# bmsMaster_power.net
KiCad netlist of a schematic drawn in Altium Designer
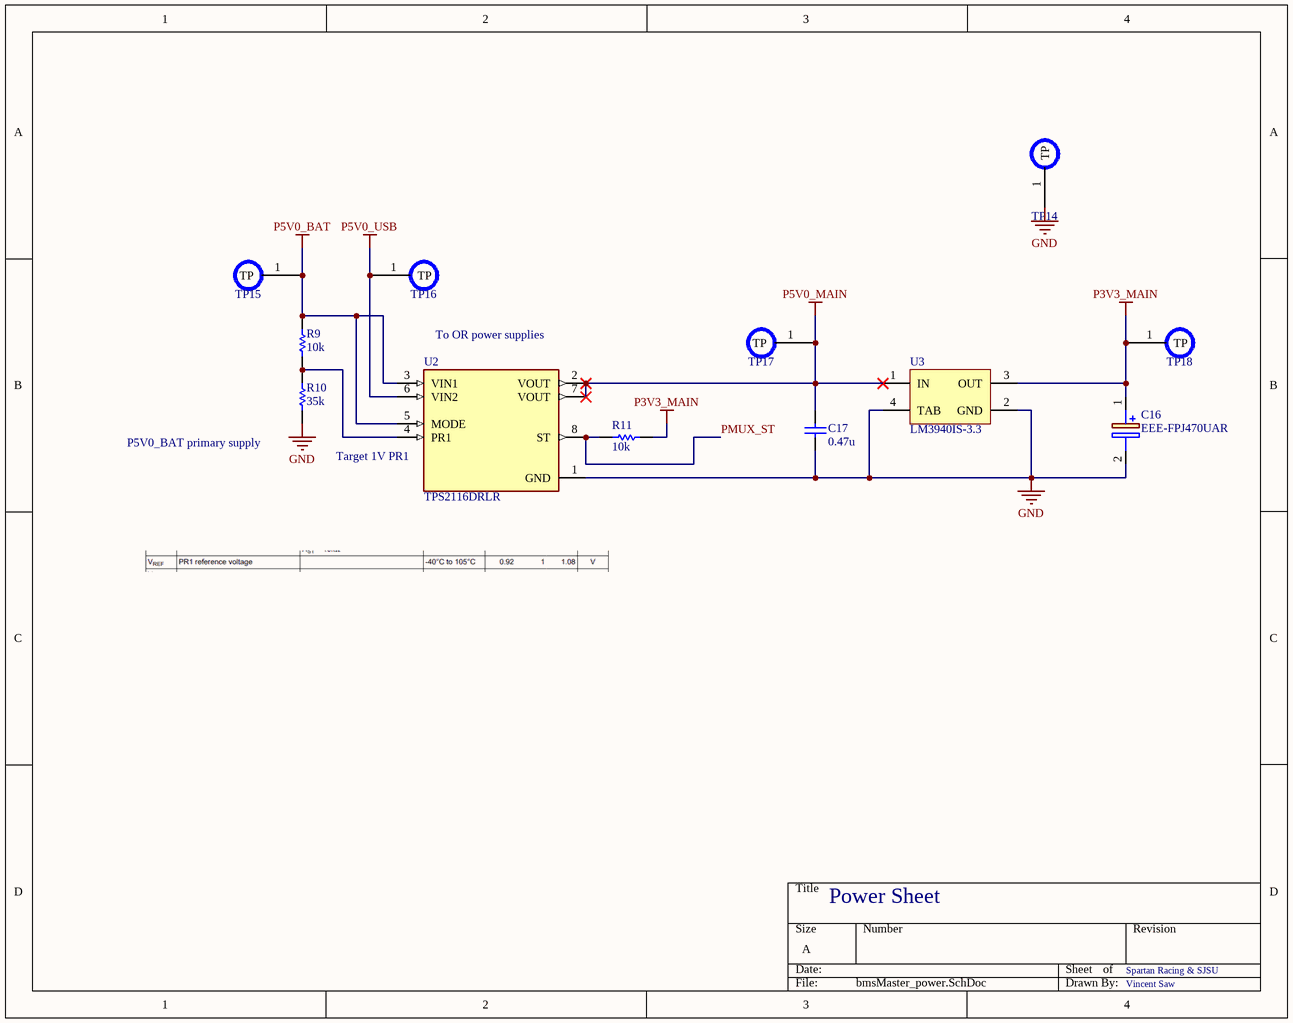
[diagram p0: bmsMaster_power.SchDoc]

(export (version "E")
  (design (tool "Eeschema 10.0.6"))
  (components
    (comp (ref "C16")
      (value "EEE-FPJ470UAR")
      (footprint "SamacSys:EEE1AA220WR")
      (description "Capacitor Polarised")
      (fields (field (name "MOUSER PART NUMBER") "667-EEE-FPJ470UAR"))
      (libsource (lib "*") (part "EEE-FPJ470UAR"))
    )
    (comp (ref "C17")
      (value "0.47u")
      (footprint "CAPC1608X90N")
      (description "Capacitor")
      (libsource (lib "Simulation Generic Components") (part "Capacitor"))
    )
    (comp (ref "R9")
      (value "10k")
      (footprint "RESC1608X50N")
      (description "Resistor")
      (libsource (lib "Simulation Generic Components") (part "Resistor"))
    )
    (comp (ref "R10")
      (value "35k")
      (footprint "RESC1608X50N")
      (description "Resistor")
      (libsource (lib "Simulation Generic Components") (part "Resistor"))
    )
    (comp (ref "R11")
      (value "10k")
      (footprint "RESC1608X50N")
      (description "Resistor")
      (libsource (lib "Simulation Generic Components") (part "Resistor"))
    )
    (comp (ref "TP14")
      (value "TSTPT")
      (footprint "Testpoint1")
      (libsource (lib "testpoint1") (part "Testpoint1"))
    )
    (comp (ref "TP15")
      (value "TSTPT")
      (footprint "Testpoint1")
      (libsource (lib "testpoint1") (part "Testpoint1"))
    )
    (comp (ref "TP16")
      (value "TSTPT")
      (footprint "Testpoint1")
      (libsource (lib "testpoint1") (part "Testpoint1"))
    )
    (comp (ref "TP17")
      (value "TSTPT")
      (footprint "Testpoint1")
      (libsource (lib "testpoint1") (part "Testpoint1"))
    )
    (comp (ref "TP18")
      (value "TSTPT")
      (footprint "Testpoint1")
      (libsource (lib "testpoint1") (part "Testpoint1"))
    )
    (comp (ref "U2")
      (value "TPS2116DRLR")
      (footprint "TPS2116DRLR:SOTFL50P160X60-8N")
      (description "1.6 V to 5.5 V, 2.5-A Low IQ Power Mux with Manual and Priority Switchover")
      (fields (field (name "MF") "{'manufacturer': u'Texas Instruments'}"))
      (libsource (lib "*") (part "TPS2116DRLR"))
    )
    (comp (ref "U3")
      (value "LM3940IS-3.3")
      (footprint "KTT0003B_N")
      (description "1A Low Dropout Regulator for 5V to 3.3V Conversion, 3-pin TO-263")
      (fields (field (name "MANUFACTURER") "Texas Instruments"))
      (libsource (lib "Altium Content Vault") (part "PM-REG-LM2940-TO4"))
    )
  )
  (nets
    (net (code "1") (name "/PMUX_ST") (class "Default")
      (node (ref "R11") (pin "2") (pinfunction "2_2") (pintype "passive"))
      (node (ref "U2") (pin "8") (pinfunction "ST_8") (pintype "output"))
    )
    (net (code "2") (name "GND") (class "Default")
      (node (ref "C16") (pin "2") (pinfunction "-_2") (pintype "passive"))
      (node (ref "C17") (pin "1") (pinfunction "1_1") (pintype "passive"))
      (node (ref "R10") (pin "1") (pinfunction "1_1") (pintype "passive"))
      (node (ref "TP14") (pin "1") (pinfunction "TP_1") (pintype "passive"))
      (node (ref "U2") (pin "1") (pinfunction "GND_1") (pintype "power_in"))
      (node (ref "U3") (pin "2") (pinfunction "GND_2") (pintype "power_in"))
      (node (ref "U3") (pin "4") (pinfunction "TAB_4") (pintype "power_in"))
    )
    (net (code "3") (name "Net-(U2-PR1)") (class "Default")
      (node (ref "R10") (pin "2") (pinfunction "2_2") (pintype "passive"))
      (node (ref "R9") (pin "1") (pinfunction "1_1") (pintype "passive"))
      (node (ref "U2") (pin "4") (pinfunction "PR1_4") (pintype "input"))
    )
    (net (code "4") (name "P3V3_MAIN") (class "Default")
      (node (ref "C16") (pin "1") (pinfunction "+_1") (pintype "passive"))
      (node (ref "R11") (pin "1") (pinfunction "1_1") (pintype "passive"))
      (node (ref "TP18") (pin "1") (pinfunction "TP_1") (pintype "passive"))
      (node (ref "U3") (pin "3") (pinfunction "OUT_3") (pintype "power_in"))
    )
    (net (code "5") (name "P5V0_BAT") (class "Default")
      (node (ref "R9") (pin "2") (pinfunction "2_2") (pintype "passive"))
      (node (ref "TP15") (pin "1") (pinfunction "TP_1") (pintype "passive"))
      (node (ref "U2") (pin "3") (pinfunction "VIN1_3") (pintype "input"))
      (node (ref "U2") (pin "5") (pinfunction "MODE_5") (pintype "input"))
    )
    (net (code "6") (name "P5V0_MAIN") (class "Default")
      (node (ref "C17") (pin "2") (pinfunction "2_2") (pintype "passive"))
      (node (ref "TP17") (pin "1") (pinfunction "TP_1") (pintype "passive"))
      (node (ref "U2") (pin "2") (pinfunction "VOUT_2") (pintype "output"))
      (node (ref "U2") (pin "7") (pinfunction "VOUT_7") (pintype "output"))
      (node (ref "U3") (pin "1") (pinfunction "IN_1") (pintype "power_in"))
    )
    (net (code "7") (name "P5V0_USB") (class "Default")
      (node (ref "TP16") (pin "1") (pinfunction "TP_1") (pintype "passive"))
      (node (ref "U2") (pin "6") (pinfunction "VIN2_6") (pintype "input"))
    )
  )
)
